# XO-Stick2.net
KiCad netlist of a schematic drawn in EAGLE
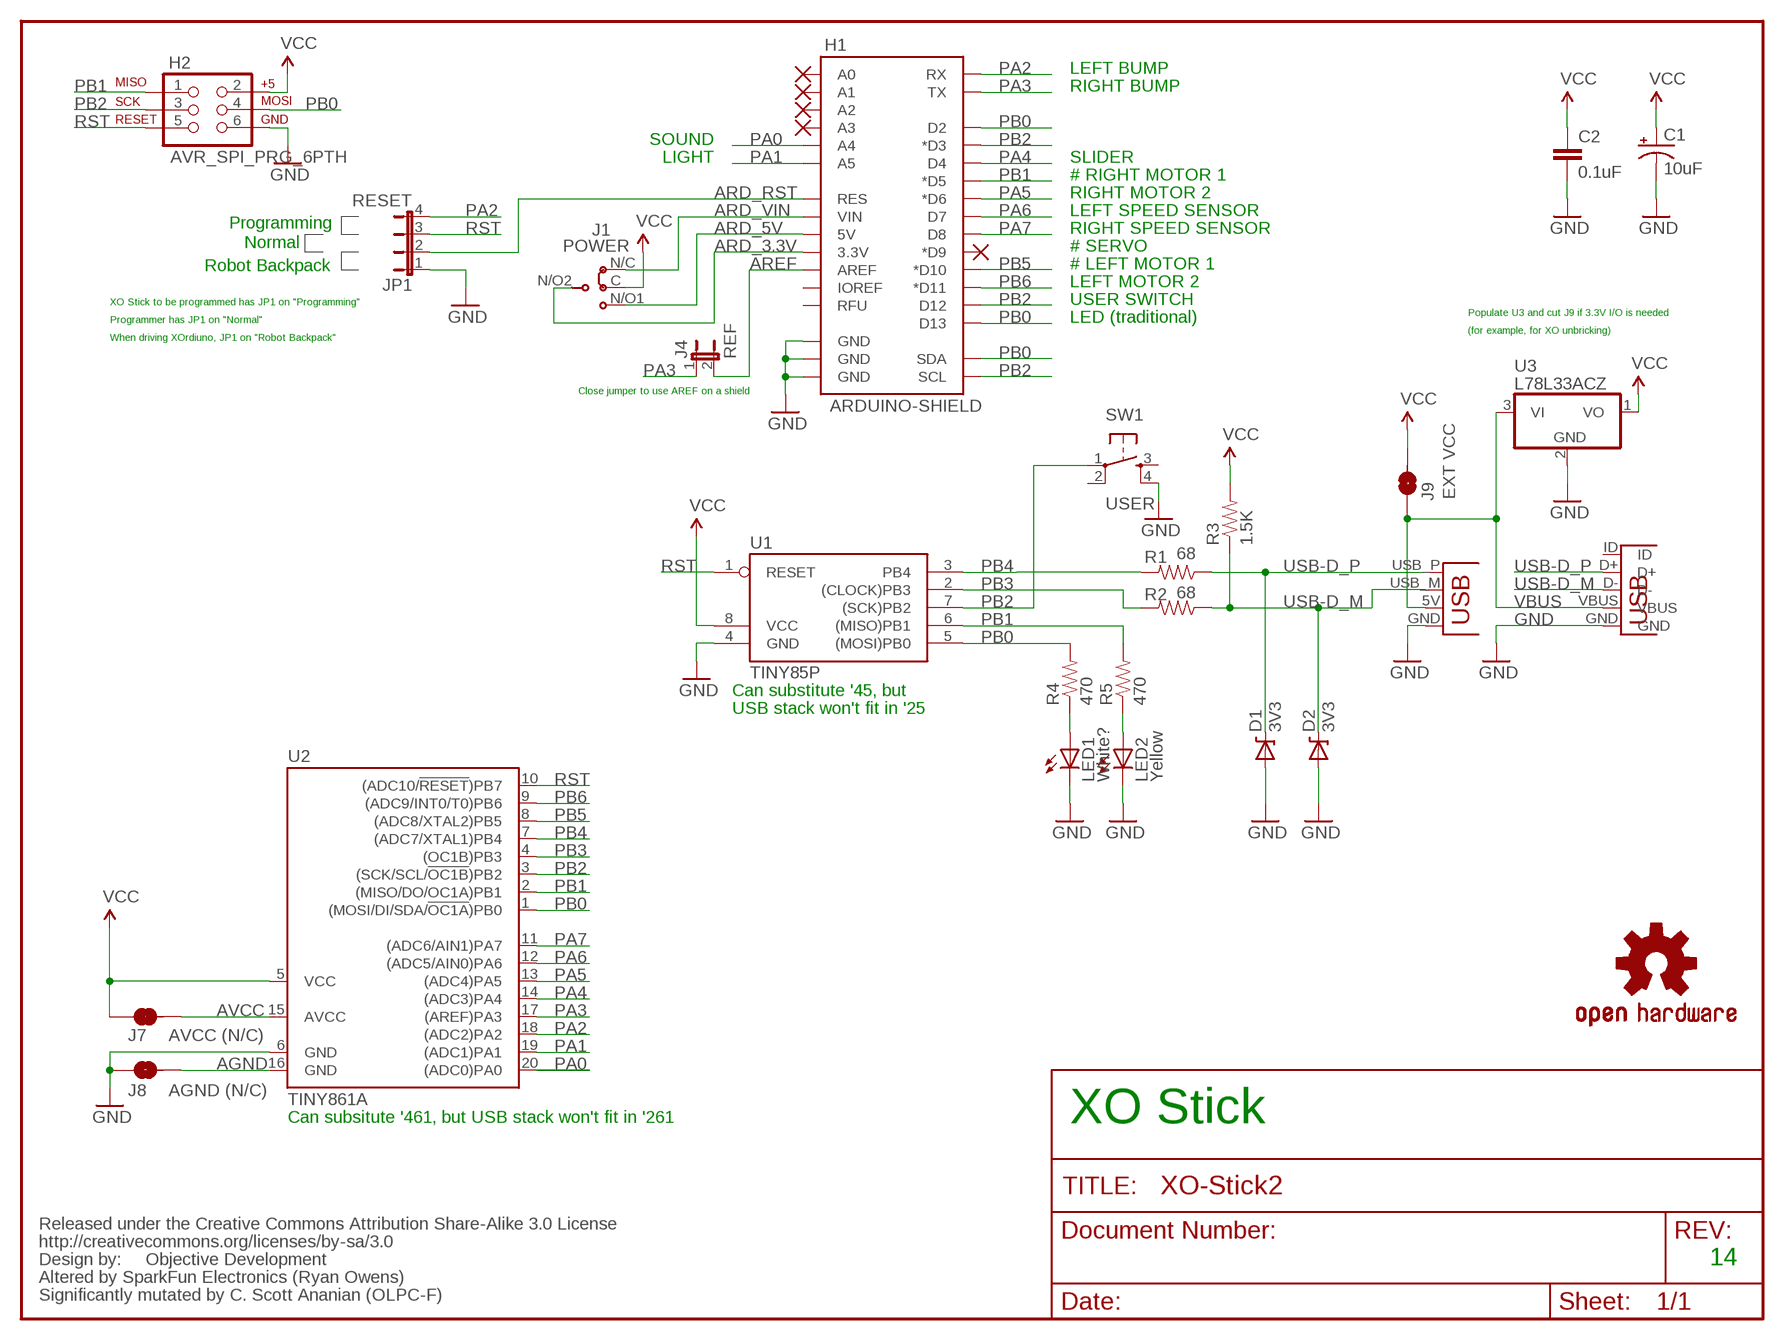
[diagram p0: schematic, sheet 1]

(export (version "E")
  (design (tool "Eeschema 10.0.6"))
  (components
    (comp (ref "C1")
      (value "10uF")
      (footprint "eagle-import:CPOL-RADIAL-10UF-25V")
      (libsource (lib "eagle-import") (part "CAP_POLPTH2"))
    )
    (comp (ref "C2")
      (value "0.1uF")
      (footprint "eagle-import:CAP-PTH-SMALL-KIT")
      (libsource (lib "eagle-import") (part "CAPKIT"))
    )
    (comp (ref "D1")
      (value "3V3")
      (footprint "eagle-import:DIODE-ZENER")
      (libsource (lib "eagle-import") (part "DIODE-ZENERPTH"))
    )
    (comp (ref "D2")
      (value "3V3")
      (footprint "eagle-import:DIODE-ZENER")
      (libsource (lib "eagle-import") (part "DIODE-ZENERPTH"))
    )
    (comp (ref "H1")
      (value "ARDUINO-SHIELD")
      (footprint "eagle-import:ARDUINO-SHIELD-VIAS-HOLES")
      (libsource (lib "eagle-import") (part "ARDUINO-SHIELD"))
    )
    (comp (ref "H2")
      (value "AVR_SPI_PRG_6PTH")
      (footprint "eagle-import:2X3")
      (libsource (lib "eagle-import") (part "AVR_SPI_PRG_6PTH"))
    )
    (comp (ref "J1")
      (value "POWER")
      (footprint "eagle-import:JP4-TRACE-NOCONFLICT")
      (libsource (lib "eagle-import") (part "JUMPER-4WAY"))
    )
    (comp (ref "J4")
      (value "REF")
      (footprint "eagle-import:SJ-2S-NO")
      (libsource (lib "eagle-import") (part "JUMPER-2SJ-NO"))
    )
    (comp (ref "J7")
      (value "AVCC (N/C)")
      (footprint "eagle-import:SJ-2S-BOT-TRACE-NOCONFLICT")
      (libsource (lib "eagle-import") (part "SOLDERJUMPERBOT-NOCONFLICT"))
    )
    (comp (ref "J8")
      (value "AGND (N/C)")
      (footprint "eagle-import:SJ-2S-BOT-TRACE-NOCONFLICT")
      (libsource (lib "eagle-import") (part "SOLDERJUMPERBOT-NOCONFLICT"))
    )
    (comp (ref "J9")
      (value "EXT VCC")
      (footprint "eagle-import:SJ-2S-BOT-TRACE-NOCONFLICT-PAD")
      (libsource (lib "eagle-import") (part "SOLDERJUMPERBOT-NOCONFLICT-PAD"))
    )
    (comp (ref "JP1")
      (value "RESET")
      (footprint "eagle-import:JP4")
      (libsource (lib "eagle-import") (part "JUMPER-4"))
    )
    (comp (ref "LED1")
      (value "White?")
      (footprint "eagle-import:LED3MM-KIT")
      (libsource (lib "eagle-import") (part "LED3MM-KIT"))
    )
    (comp (ref "LED2")
      (value "Yellow")
      (footprint "eagle-import:LED3MM-KIT")
      (libsource (lib "eagle-import") (part "LED3MM-KIT"))
    )
    (comp (ref "R1")
      (value "68")
      (footprint "eagle-import:AXIAL-0.3-KIT")
      (libsource (lib "eagle-import") (part "RESISTORKIT"))
    )
    (comp (ref "R2")
      (value "68")
      (footprint "eagle-import:AXIAL-0.3-KIT")
      (libsource (lib "eagle-import") (part "RESISTORKIT"))
    )
    (comp (ref "R3")
      (value "1.5K")
      (footprint "eagle-import:AXIAL-0.3-KIT")
      (libsource (lib "eagle-import") (part "RESISTORKIT"))
    )
    (comp (ref "R4")
      (value "470")
      (footprint "eagle-import:AXIAL-0.3-KIT")
      (libsource (lib "eagle-import") (part "RESISTORKIT"))
    )
    (comp (ref "R5")
      (value "470")
      (footprint "eagle-import:AXIAL-0.3-KIT")
      (libsource (lib "eagle-import") (part "RESISTORKIT"))
    )
    (comp (ref "SW1")
      (value "USER")
      (footprint "eagle-import:TACTILE-PTH")
      (libsource (lib "eagle-import") (part "TAC_SWITCHPTH"))
    )
    (comp (ref "U$1")
      (value "OSHW-LOGOM")
      (footprint "eagle-import:OSHW-LOGO-M")
      (libsource (lib "eagle-import") (part "OSHW-LOGOM"))
    )
    (comp (ref "U$4")
      (value "CREATIVE_COMMONS")
      (footprint "eagle-import:CREATIVE_COMMONS")
      (libsource (lib "eagle-import") (part "CREATIVE_COMMONS"))
    )
    (comp (ref "U1")
      (value "TINY85P")
      (footprint "eagle-import:DIL08")
      (libsource (lib "eagle-import") (part "TINY85P"))
    )
    (comp (ref "U2")
      (value "TINY861A")
      (footprint "eagle-import:DIL20")
      (fields (field (name "MPN") "ATTINY26L-8PU"))
      (libsource (lib "eagle-import") (part "TINY26PL"))
    )
    (comp (ref "U3")
      (value "L78L33ACZ")
      (footprint "eagle-import:TO92")
      (libsource (lib "eagle-import") (part "78ZL05"))
    )
    (comp (ref "X1")
      (value "USBPCB")
      (footprint "eagle-import:USB-A-PCB")
      (libsource (lib "eagle-import") (part "USBPCB"))
    )
    (comp (ref "X2")
      (value "USBMINIB")
      (footprint "eagle-import:USB-MB-H2")
      (libsource (lib "eagle-import") (part "USBMINIB"))
    )
  )
  (nets
    (net (code "1") (name "/AGND") (class "Default")
      (node (ref "J8") (pin "2") (pinfunction "2_2") (pintype "passive"))
      (node (ref "U2") (pin "16") (pinfunction "GND_16") (pintype "power_in"))
    )
    (net (code "2") (name "/ARD_3.3V") (class "Default")
      (node (ref "H1") (pin "3.3V") (pinfunction "3.3V_3.3V") (pintype "bidirectional"))
      (node (ref "J1") (pin "N/O2") (pinfunction "N/O2_N/O2") (pintype "passive"))
    )
    (net (code "3") (name "/ARD_5V") (class "Default")
      (node (ref "H1") (pin "5V") (pinfunction "5V_5V") (pintype "bidirectional"))
      (node (ref "J1") (pin "N/O1") (pinfunction "N/O1_N/O1") (pintype "passive"))
    )
    (net (code "4") (name "/ARD_RST") (class "Default")
      (node (ref "H1") (pin "RES") (pinfunction "RES_RES") (pintype "bidirectional"))
      (node (ref "JP1") (pin "2") (pinfunction "2_2") (pintype "passive"))
    )
    (net (code "5") (name "/ARD_VIN") (class "Default")
      (node (ref "H1") (pin "VIN") (pinfunction "VIN_VIN") (pintype "bidirectional"))
      (node (ref "J1") (pin "N/C") (pinfunction "N/C_N/C") (pintype "passive"))
    )
    (net (code "6") (name "/AREF") (class "Default")
      (node (ref "H1") (pin "AREF") (pinfunction "AREF_AREF") (pintype "bidirectional"))
      (node (ref "J4") (pin "2") (pinfunction "2_2") (pintype "passive"))
    )
    (net (code "7") (name "/AVCC") (class "Default")
      (node (ref "J7") (pin "2") (pinfunction "2_2") (pintype "passive"))
      (node (ref "U2") (pin "15") (pinfunction "AVCC_15") (pintype "power_in"))
    )
    (net (code "8") (name "/PA0") (class "Default")
      (node (ref "H1") (pin "A4") (pinfunction "A4_A4") (pintype "bidirectional"))
      (node (ref "U2") (pin "20") (pinfunction "(ADC0)PA0_20") (pintype "bidirectional"))
    )
    (net (code "9") (name "/PA1") (class "Default")
      (node (ref "H1") (pin "A5") (pinfunction "A5_A5") (pintype "bidirectional"))
      (node (ref "U2") (pin "19") (pinfunction "(ADC1)PA1_19") (pintype "bidirectional"))
    )
    (net (code "10") (name "/PA2") (class "Default")
      (node (ref "H1") (pin "RX") (pinfunction "RX_RX") (pintype "bidirectional"))
      (node (ref "JP1") (pin "4") (pinfunction "4_4") (pintype "passive"))
      (node (ref "U2") (pin "18") (pinfunction "(ADC2)PA2_18") (pintype "bidirectional"))
    )
    (net (code "11") (name "/PA3") (class "Default")
      (node (ref "H1") (pin "TX") (pinfunction "TX_TX") (pintype "bidirectional"))
      (node (ref "J4") (pin "1") (pinfunction "1_1") (pintype "passive"))
      (node (ref "U2") (pin "17") (pinfunction "(AREF)PA3_17") (pintype "bidirectional"))
    )
    (net (code "12") (name "/PA4") (class "Default")
      (node (ref "H1") (pin "D4") (pinfunction "D4_D4") (pintype "bidirectional"))
      (node (ref "U2") (pin "14") (pinfunction "(ADC3)PA4_14") (pintype "bidirectional"))
    )
    (net (code "13") (name "/PA5") (class "Default")
      (node (ref "H1") (pin "D6") (pinfunction "*D6_D6") (pintype "bidirectional"))
      (node (ref "U2") (pin "13") (pinfunction "(ADC4)PA5_13") (pintype "bidirectional"))
    )
    (net (code "14") (name "/PA6") (class "Default")
      (node (ref "H1") (pin "D7") (pinfunction "D7_D7") (pintype "bidirectional"))
      (node (ref "U2") (pin "12") (pinfunction "(ADC5/AIN0)PA6_12") (pintype "bidirectional"))
    )
    (net (code "15") (name "/PA7") (class "Default")
      (node (ref "H1") (pin "D8") (pinfunction "D8_D8") (pintype "bidirectional"))
      (node (ref "U2") (pin "11") (pinfunction "(ADC6/AIN1)PA7_11") (pintype "bidirectional"))
    )
    (net (code "16") (name "/PB0") (class "Default")
      (node (ref "H1") (pin "D13") (pinfunction "D13_D13") (pintype "bidirectional"))
      (node (ref "H1") (pin "D2") (pinfunction "D2_D2") (pintype "bidirectional"))
      (node (ref "H1") (pin "SDA") (pinfunction "SDA_SDA") (pintype "bidirectional"))
      (node (ref "H2") (pin "4") (pinfunction "4_4") (pintype "passive"))
      (node (ref "R4") (pin "P$2") (pinfunction "2_P$2") (pintype "passive"))
      (node (ref "U1") (pin "5") (pinfunction "(MOSI)PB0_5") (pintype "bidirectional"))
      (node (ref "U2") (pin "1") (pinfunction "(MOSI/DI/SDA/~{OC1A})PB0_1") (pintype "bidirectional"))
    )
    (net (code "17") (name "/PB1") (class "Default")
      (node (ref "H1") (pin "D5") (pinfunction "*D5_D5") (pintype "bidirectional"))
      (node (ref "H2") (pin "1") (pinfunction "1_1") (pintype "passive"))
      (node (ref "R5") (pin "P$2") (pinfunction "2_P$2") (pintype "passive"))
      (node (ref "U1") (pin "6") (pinfunction "(MISO)PB1_6") (pintype "bidirectional"))
      (node (ref "U2") (pin "2") (pinfunction "(MISO/DO/OC1A)PB1_2") (pintype "bidirectional"))
    )
    (net (code "18") (name "/PB2") (class "Default")
      (node (ref "H1") (pin "D12") (pinfunction "D12_D12") (pintype "bidirectional"))
      (node (ref "H1") (pin "D3") (pinfunction "*D3_D3") (pintype "bidirectional"))
      (node (ref "H1") (pin "SCL") (pinfunction "SCL_SCL") (pintype "bidirectional"))
      (node (ref "H2") (pin "3") (pinfunction "3_3") (pintype "passive"))
      (node (ref "SW1") (pin "1") (pinfunction "1_1") (pintype "passive"))
      (node (ref "U1") (pin "7") (pinfunction "(SCK)PB2_7") (pintype "bidirectional"))
      (node (ref "U2") (pin "3") (pinfunction "(SCK/SCL/~{OC1B})PB2_3") (pintype "bidirectional"))
    )
    (net (code "19") (name "/PB3") (class "Default")
      (node (ref "R2") (pin "P$2") (pinfunction "2_P$2") (pintype "passive"))
      (node (ref "U1") (pin "2") (pinfunction "(CLOCK)PB3_2") (pintype "bidirectional"))
      (node (ref "U2") (pin "4") (pinfunction "(OC1B)PB3_4") (pintype "bidirectional"))
    )
    (net (code "20") (name "/PB4") (class "Default")
      (node (ref "R1") (pin "P$2") (pinfunction "2_P$2") (pintype "passive"))
      (node (ref "U1") (pin "3") (pinfunction "PB4_3") (pintype "bidirectional"))
      (node (ref "U2") (pin "7") (pinfunction "(ADC7/XTAL1)PB4_7") (pintype "bidirectional"))
    )
    (net (code "21") (name "/PB5") (class "Default")
      (node (ref "H1") (pin "D10") (pinfunction "*D10_D10") (pintype "bidirectional"))
      (node (ref "U2") (pin "8") (pinfunction "(ADC8/XTAL2)PB5_8") (pintype "bidirectional"))
    )
    (net (code "22") (name "/PB6") (class "Default")
      (node (ref "H1") (pin "D11") (pinfunction "*D11_D11") (pintype "bidirectional"))
      (node (ref "U2") (pin "9") (pinfunction "(ADC9/INT0/T0)PB6_9") (pintype "bidirectional"))
    )
    (net (code "23") (name "/RST") (class "Default")
      (node (ref "H2") (pin "5") (pinfunction "5_5") (pintype "passive"))
      (node (ref "JP1") (pin "3") (pinfunction "3_3") (pintype "passive"))
      (node (ref "U1") (pin "1") (pinfunction "RESET_1") (pintype "input"))
      (node (ref "U2") (pin "10") (pinfunction "(ADC10/~{RESET})PB7_10") (pintype "bidirectional"))
    )
    (net (code "24") (name "/USB-D_M") (class "Default")
      (node (ref "D2") (pin "P$1") (pinfunction "C_P$1") (pintype "passive"))
      (node (ref "R2") (pin "P$1") (pinfunction "1_P$1") (pintype "passive"))
      (node (ref "R3") (pin "P$1") (pinfunction "1_P$1") (pintype "passive"))
      (node (ref "X1") (pin "USB_M") (pinfunction "D-_USB_M") (pintype "bidirectional"))
      (node (ref "X2") (pin "D-") (pinfunction "D-_D-") (pintype "bidirectional"))
    )
    (net (code "25") (name "/USB-D_P") (class "Default")
      (node (ref "D1") (pin "P$1") (pinfunction "C_P$1") (pintype "passive"))
      (node (ref "R1") (pin "P$1") (pinfunction "1_P$1") (pintype "passive"))
      (node (ref "X1") (pin "USB_P") (pinfunction "D+_USB_P") (pintype "bidirectional"))
      (node (ref "X2") (pin "D+") (pinfunction "D+_D+") (pintype "bidirectional"))
    )
    (net (code "26") (name "/VBUS") (class "Default")
      (node (ref "J9") (pin "1") (pinfunction "1_1") (pintype "passive"))
      (node (ref "U3") (pin "3") (pinfunction "VI_3") (pintype "input"))
      (node (ref "X1") (pin "5V") (pinfunction "VBUS_5V") (pintype "bidirectional"))
      (node (ref "X2") (pin "VBUS") (pinfunction "VBUS_VBUS") (pintype "bidirectional"))
    )
    (net (code "27") (name "GND") (class "Default")
      (node (ref "C1") (pin "2") (pinfunction "-_2") (pintype "passive"))
      (node (ref "C2") (pin "2") (pinfunction "2_2") (pintype "passive"))
      (node (ref "D1") (pin "P$2") (pinfunction "A_P$2") (pintype "passive"))
      (node (ref "D2") (pin "P$2") (pinfunction "A_P$2") (pintype "passive"))
      (node (ref "H1") (pin "GND@0") (pinfunction "GND_GND@0") (pintype "bidirectional"))
      (node (ref "H1") (pin "GND@1") (pinfunction "GND_GND@1") (pintype "bidirectional"))
      (node (ref "H1") (pin "GND@2") (pinfunction "GND_GND@2") (pintype "bidirectional"))
      (node (ref "H2") (pin "6") (pinfunction "6_6") (pintype "passive"))
      (node (ref "J8") (pin "1") (pinfunction "1_1") (pintype "passive"))
      (node (ref "JP1") (pin "1") (pinfunction "1_1") (pintype "passive"))
      (node (ref "LED1") (pin "K") (pinfunction "C_K") (pintype "passive"))
      (node (ref "LED2") (pin "K") (pinfunction "C_K") (pintype "passive"))
      (node (ref "SW1") (pin "4") (pinfunction "4_4") (pintype "passive"))
      (node (ref "U1") (pin "4") (pinfunction "GND_4") (pintype "power_in"))
      (node (ref "U2") (pin "6") (pinfunction "GND_6") (pintype "power_in"))
      (node (ref "U3") (pin "2") (pinfunction "GND_2") (pintype "passive"))
      (node (ref "X1") (pin "GND") (pinfunction "GND_GND") (pintype "bidirectional"))
      (node (ref "X2") (pin "GND") (pinfunction "GND_GND") (pintype "bidirectional"))
    )
    (net (code "28") (name "Net-(R4-1)") (class "Default")
      (node (ref "LED1") (pin "A") (pinfunction "A_A") (pintype "passive"))
      (node (ref "R4") (pin "P$1") (pinfunction "1_P$1") (pintype "passive"))
    )
    (net (code "29") (name "Net-(R5-1)") (class "Default")
      (node (ref "LED2") (pin "A") (pinfunction "A_A") (pintype "passive"))
      (node (ref "R5") (pin "P$1") (pinfunction "1_P$1") (pintype "passive"))
    )
    (net (code "30") (name "VCC") (class "Default")
      (node (ref "C1") (pin "1") (pinfunction "+_1") (pintype "passive"))
      (node (ref "C2") (pin "1") (pinfunction "1_1") (pintype "passive"))
      (node (ref "H2") (pin "2") (pinfunction "2_2") (pintype "passive"))
      (node (ref "J1") (pin "C") (pinfunction "C_C") (pintype "passive"))
      (node (ref "J7") (pin "1") (pinfunction "1_1") (pintype "passive"))
      (node (ref "J9") (pin "2") (pinfunction "2_2") (pintype "passive"))
      (node (ref "R3") (pin "P$2") (pinfunction "2_P$2") (pintype "passive"))
      (node (ref "U1") (pin "8") (pinfunction "VCC_8") (pintype "power_in"))
      (node (ref "U2") (pin "5") (pinfunction "VCC_5") (pintype "power_in"))
      (node (ref "U3") (pin "1") (pinfunction "VO_1") (pintype "passive"))
    )
    (net (code "31") (name "unconnected-(H1-*D9-PadD9)") (class "Default")
      (node (ref "H1") (pin "D9") (pinfunction "*D9_D9") (pintype "bidirectional"))
    )
    (net (code "32") (name "unconnected-(H1-PadA0)") (class "Default")
      (node (ref "H1") (pin "A0") (pinfunction "A0_A0") (pintype "bidirectional"))
    )
    (net (code "33") (name "unconnected-(H1-PadA1)") (class "Default")
      (node (ref "H1") (pin "A1") (pinfunction "A1_A1") (pintype "bidirectional"))
    )
    (net (code "34") (name "unconnected-(H1-PadA2)") (class "Default")
      (node (ref "H1") (pin "A2") (pinfunction "A2_A2") (pintype "bidirectional"))
    )
    (net (code "35") (name "unconnected-(H1-PadA3)") (class "Default")
      (node (ref "H1") (pin "A3") (pinfunction "A3_A3") (pintype "bidirectional"))
    )
    (net (code "36") (name "unconnected-(H1-PadIOREF)") (class "Default")
      (node (ref "H1") (pin "IOREF") (pinfunction "IOREF_IOREF") (pintype "bidirectional"))
    )
    (net (code "37") (name "unconnected-(H1-PadRFU)") (class "Default")
      (node (ref "H1") (pin "RFU") (pinfunction "RFU_RFU") (pintype "bidirectional"))
    )
    (net (code "38") (name "unconnected-(SW1-Pad2)") (class "Default")
      (node (ref "SW1") (pin "2") (pinfunction "2_2") (pintype "passive"))
    )
    (net (code "39") (name "unconnected-(SW1-Pad3)") (class "Default")
      (node (ref "SW1") (pin "3") (pinfunction "3_3") (pintype "passive"))
    )
    (net (code "40") (name "unconnected-(X2-PadID)") (class "Default")
      (node (ref "X2") (pin "ID") (pinfunction "ID_ID") (pintype "bidirectional"))
    )
  )
)
